# P15-EXP_IO.net
KiCad netlist of a schematic drawn in Altium Designer
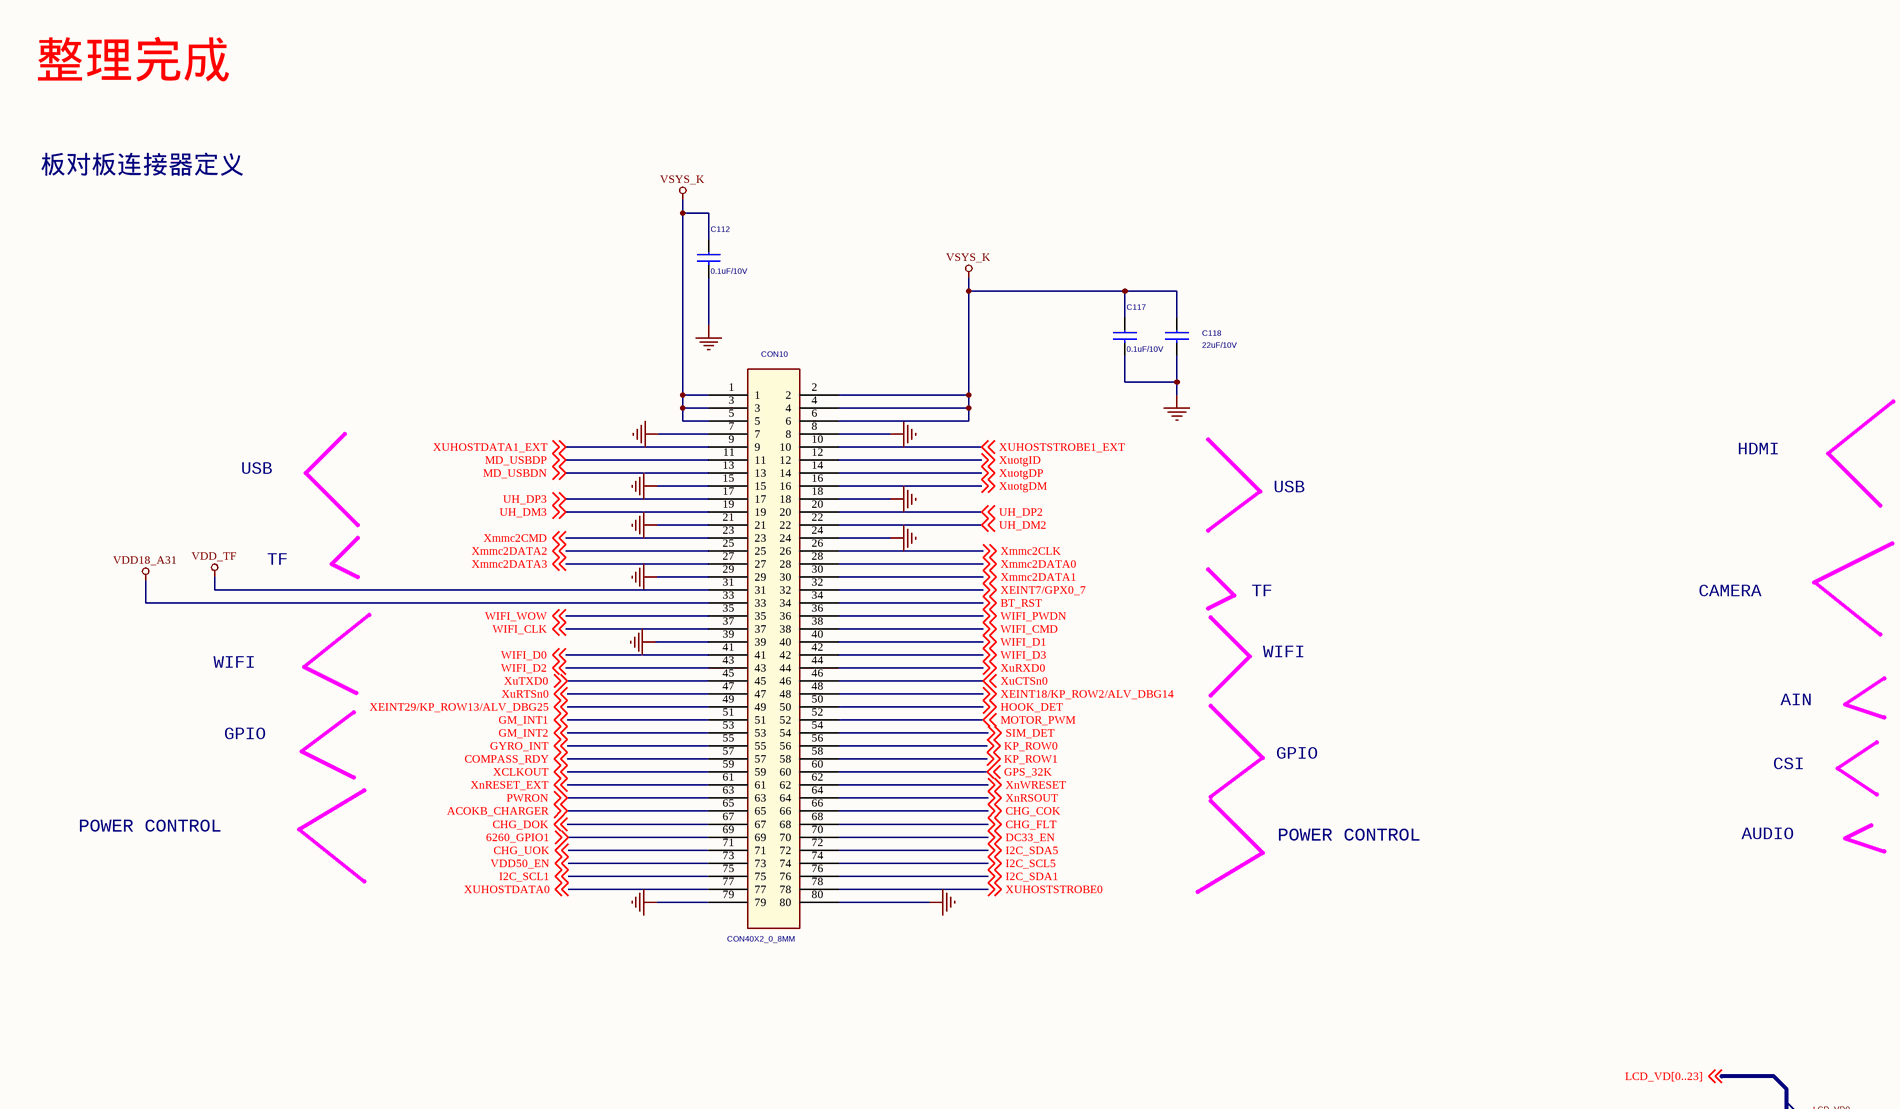
[diagram p0: P15-EXP_IO.SchDoc, top left]
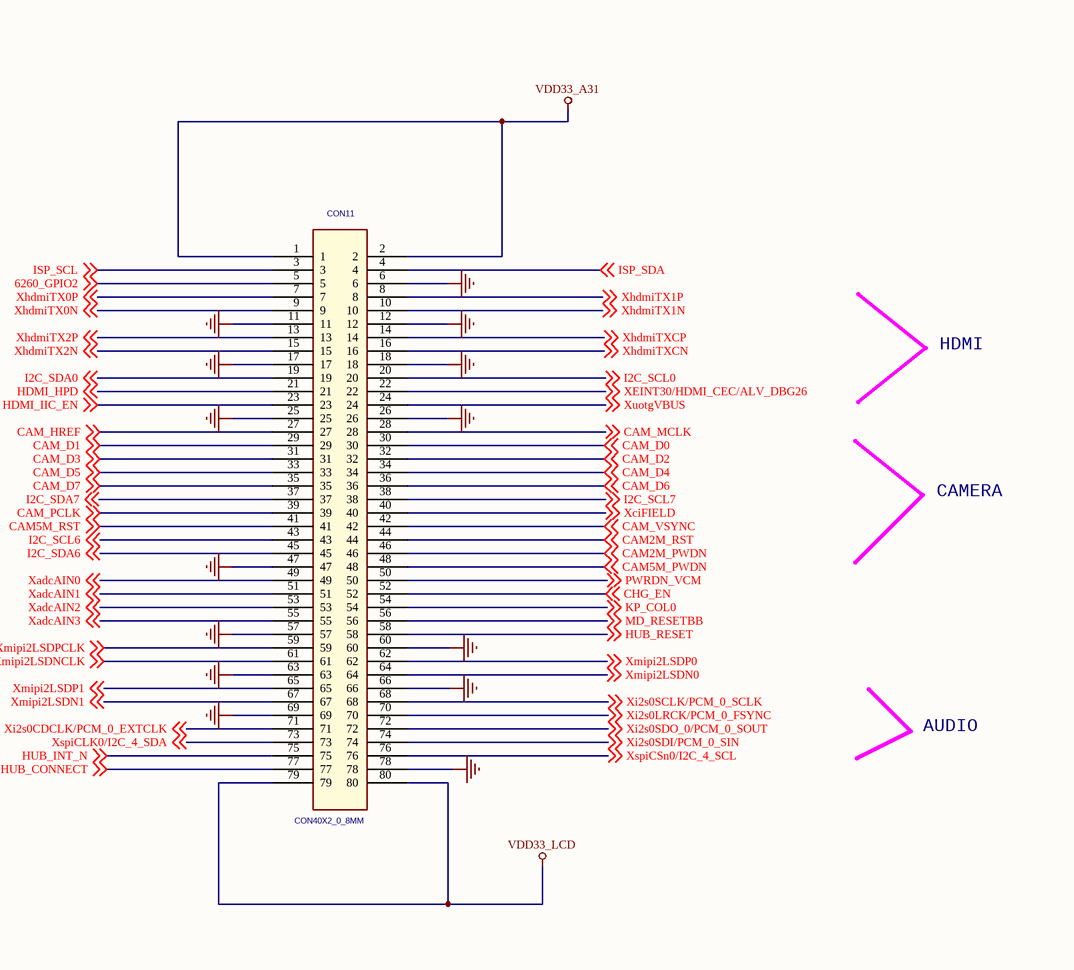
[diagram p1: P15-EXP_IO.SchDoc, top right]
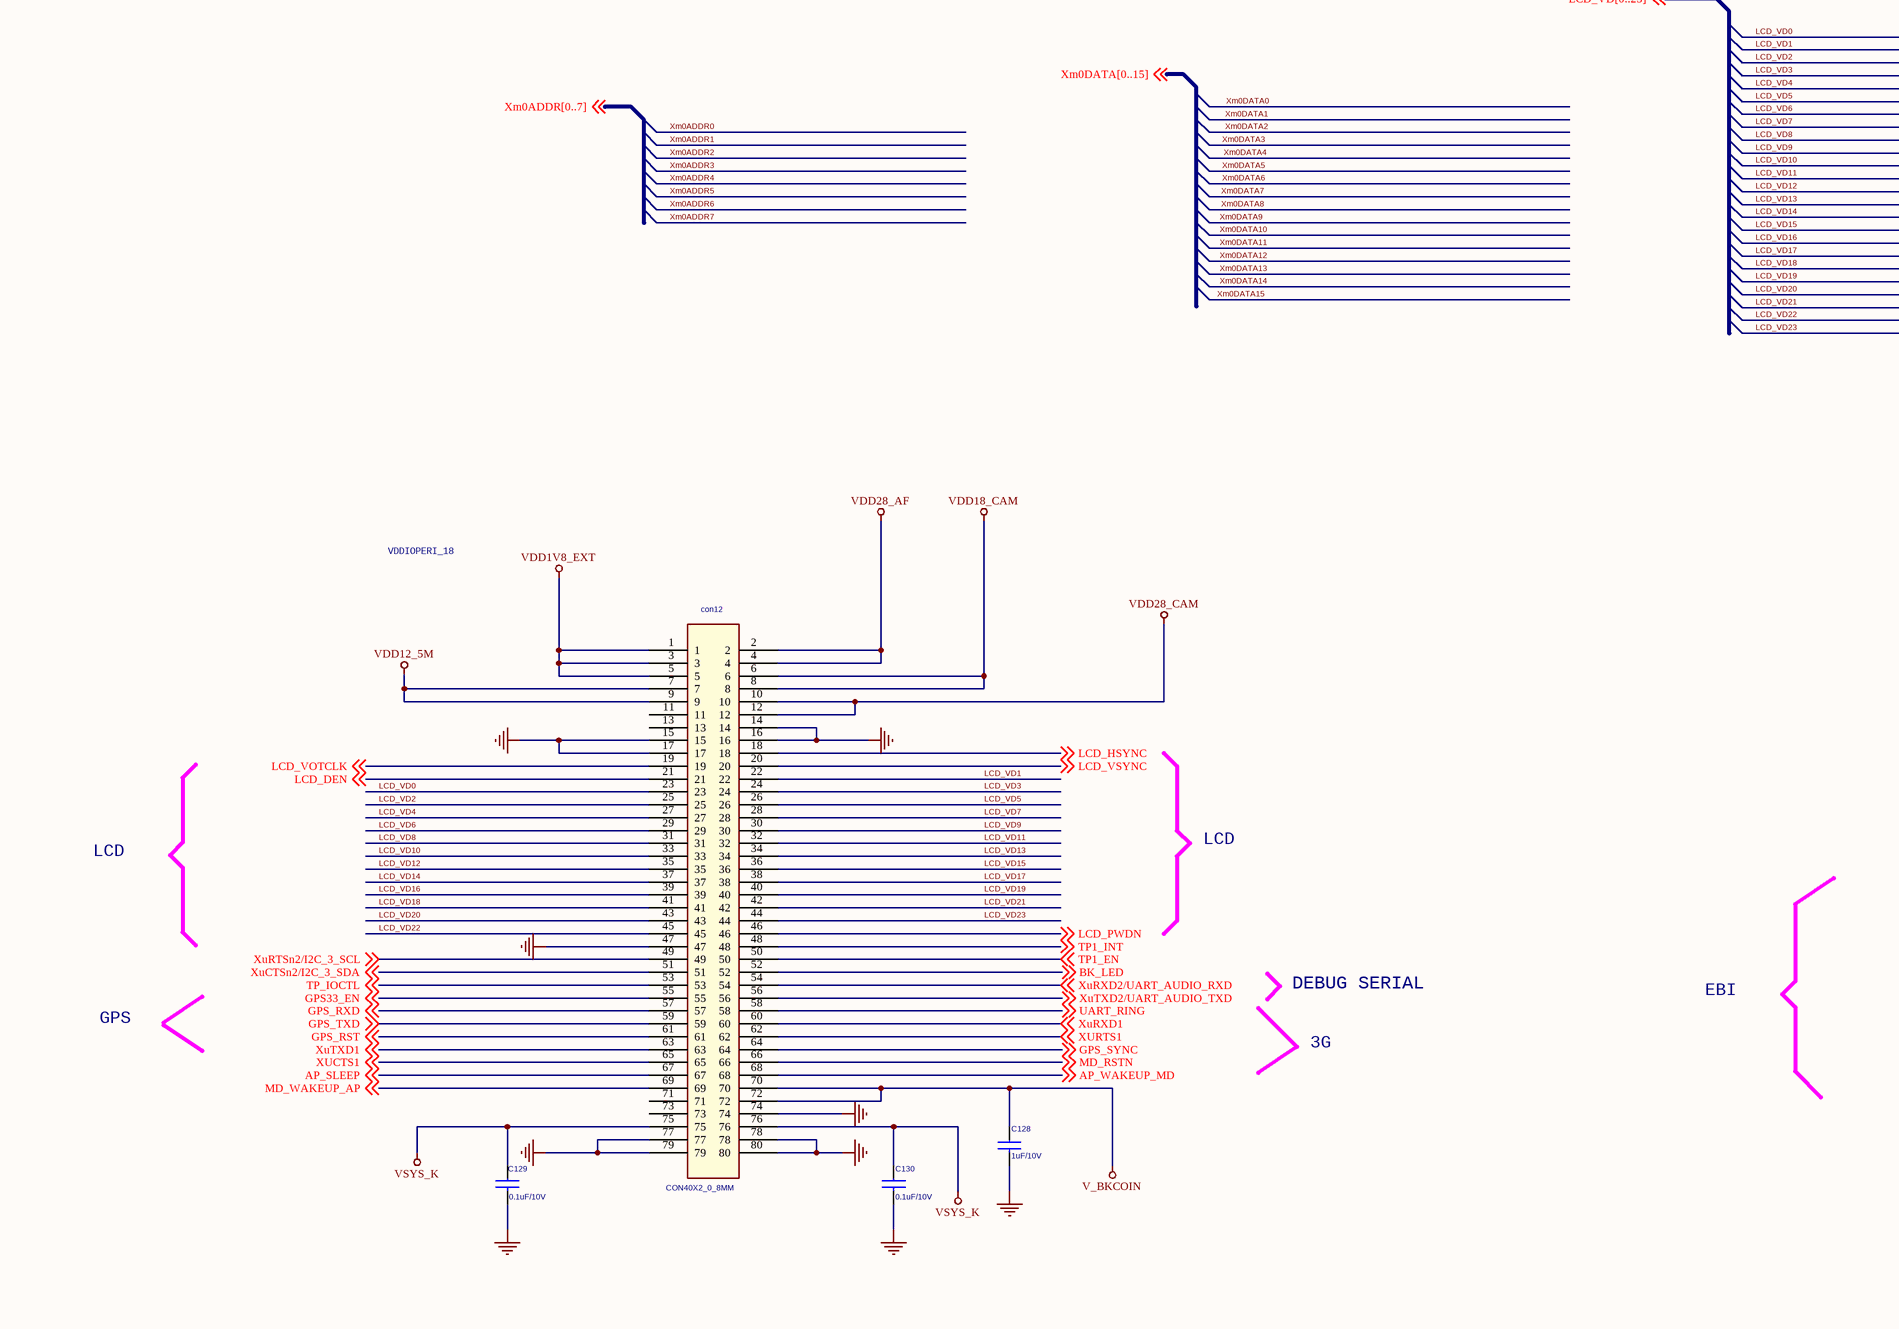
[diagram p2: P15-EXP_IO.SchDoc, bottom left]
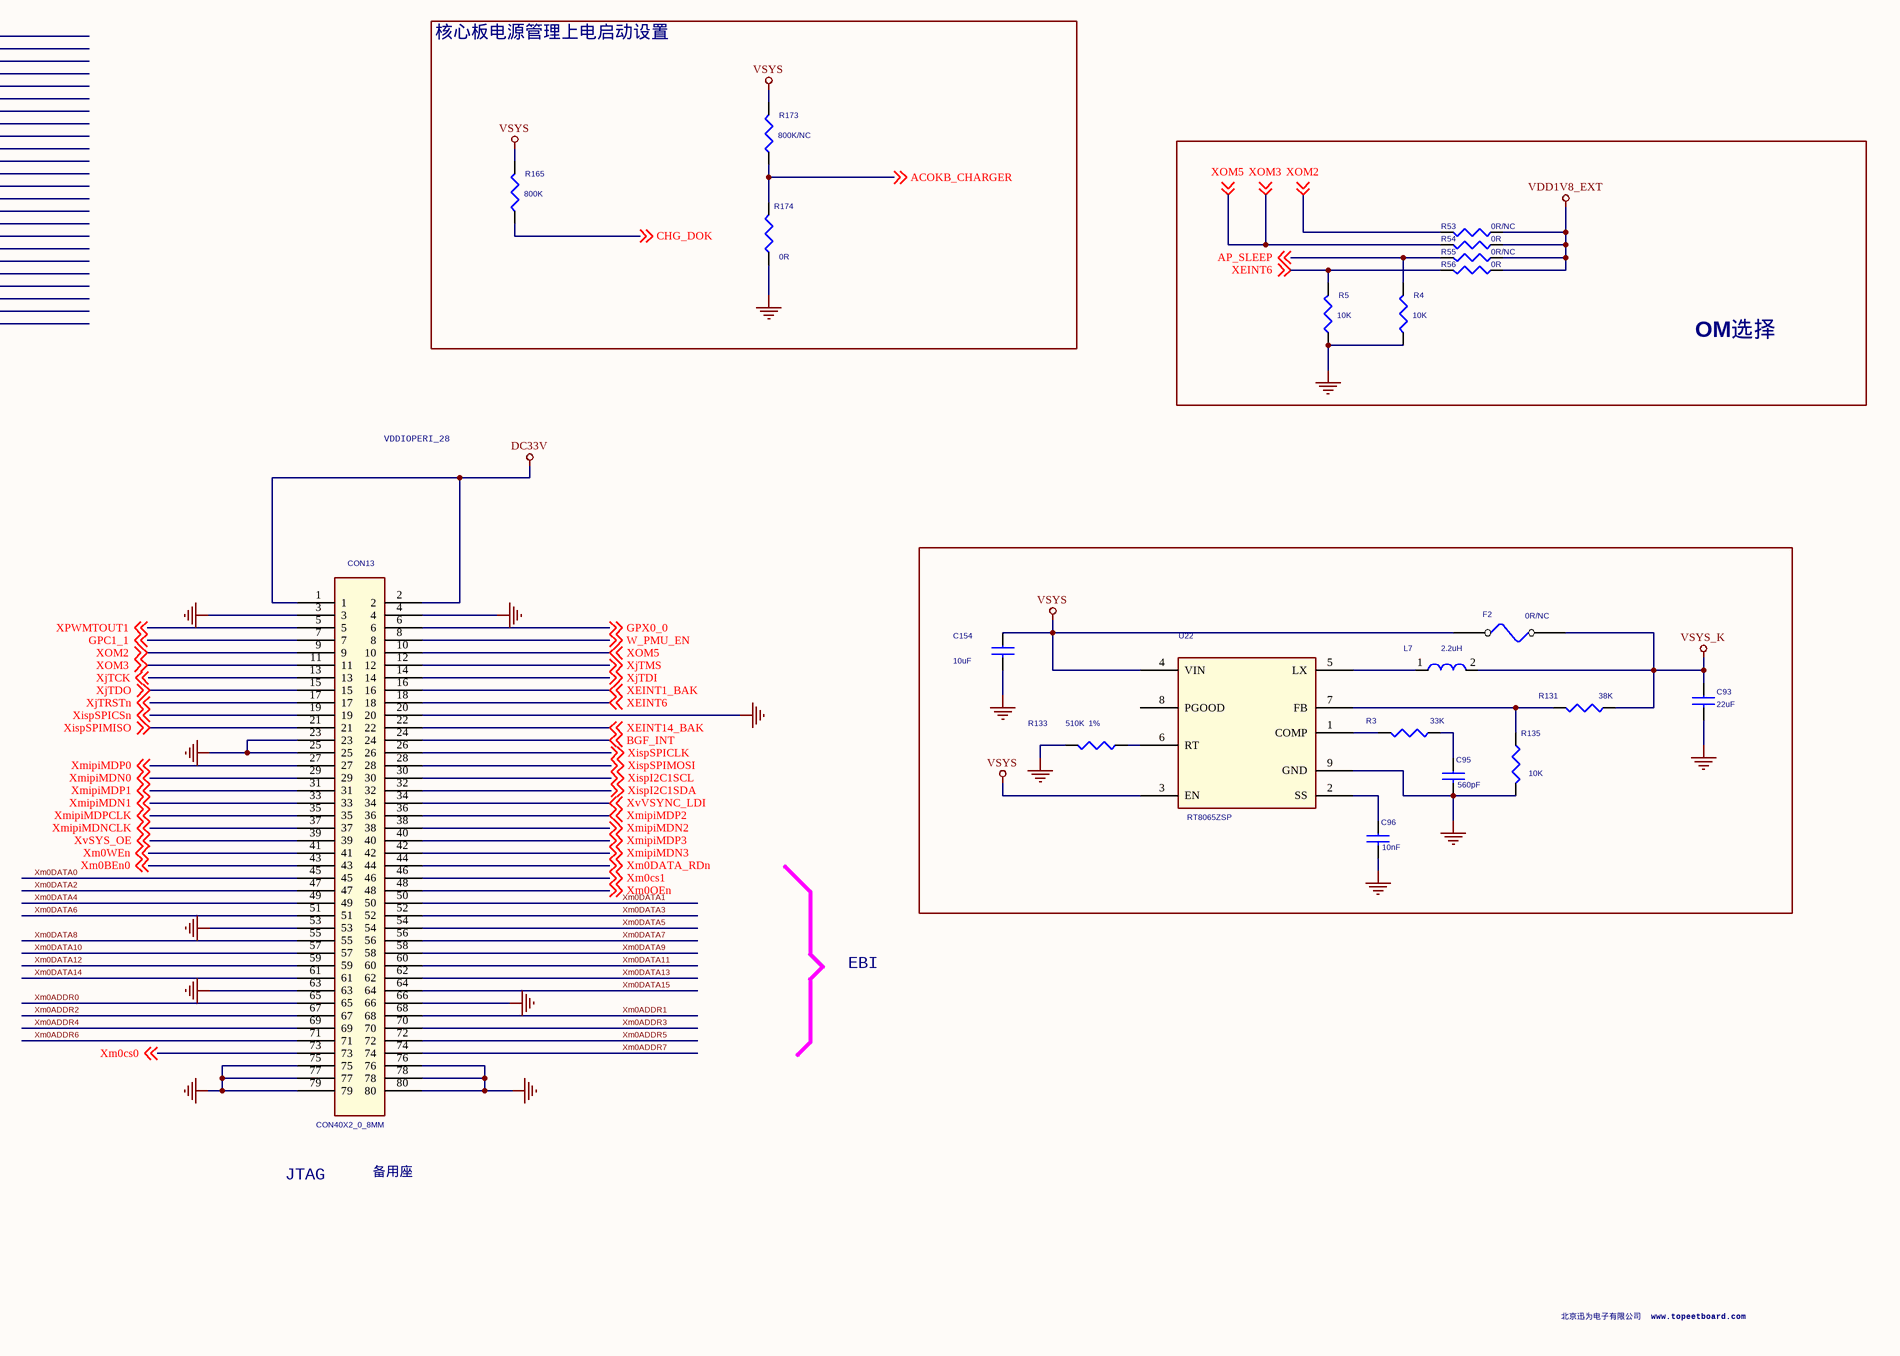
[diagram p3: P15-EXP_IO.SchDoc, bottom right]

(export (version "E")
  (design (tool "Eeschema 10.0.6"))
  (components
    (comp (ref "C93") (value "22uF") (footprint "C0805-S") (libsource (lib "*") (part "C1005")))
    (comp (ref "C95")
      (value "560pF")
      (footprint "C0603-S")
      (description "CER CHIP 1U 10% X5R 0402 10V  L/F")
      (fields (field (name "PART_NUMBER") "06-210594-01"))
      (libsource (lib "*") (part "CAP NP_3"))
    )
    (comp (ref "C96")
      (value "10nF")
      (footprint "C0603-S")
      (description "CER CHIP 1U 10% X5R 0402 10V  L/F")
      (fields (field (name "PART_NUMBER") "06-210594-01"))
      (libsource (lib "*") (part "CAP NP_3"))
    )
    (comp (ref "C112") (value "0.1uF/10V") (footprint "C0603-S") (libsource (lib "*") (part "C0402_0")))
    (comp (ref "C117") (value "0.1uF/10V") (footprint "C0603-S") (libsource (lib "*") (part "C0402_0")))
    (comp (ref "C118") (value "22uF/10V") (footprint "C1206-S") (libsource (lib "*") (part "C1206_0")))
    (comp (ref "C128") (value "1uF/10V") (footprint "C0603-S") (libsource (lib "*") (part "C0603_0")))
    (comp (ref "C129") (value "0.1uF/10V") (footprint "C0603-S") (libsource (lib "*") (part "C0402_0")))
    (comp (ref "C130") (value "0.1uF/10V") (footprint "C0603-S") (libsource (lib "*") (part "C0402_0")))
    (comp (ref "C154")
      (value "10uF")
      (footprint "C0603-S")
      (description "CER CHIP 1U 10% X5R 0402 10V  L/F")
      (fields (field (name "PART_NUMBER") "06-210594-01"))
      (libsource (lib "*") (part "CAP NP_3"))
    )
    (comp (ref "CON10") (value "CON40X2_0_8MM") (libsource (lib "*") (part "CON40X2_0_8MM")))
    (comp (ref "CON11") (value "CON40X2_0_8MM") (libsource (lib "*") (part "CON40X2_0_8MM")))
    (comp (ref "con12")
      (value "CON40X2_0_8MM")
      (footprint "CON2X40-0_5MM-BB")
      (libsource (lib "*") (part "CON40X2_0_8MM"))
    )
    (comp (ref "CON13") (value "CON40X2_0_8MM") (libsource (lib "*") (part "CON40X2_0_8MM")))
    (comp (ref "F2") (value "0R/NC") (libsource (lib "*") (part "FUSE")))
    (comp (ref "L7") (value "2.2uH") (footprint "L3X3MM") (libsource (lib "*") (part "LQH32C_0")))
    (comp (ref "R3") (value "33K") (footprint "R0603-S") (libsource (lib "*") (part "R1005_0")))
    (comp (ref "R4") (value "10K") (footprint "R0603-S") (libsource (lib "*") (part "R1005_0_Dup1")))
    (comp (ref "R5") (value "10K") (footprint "R0603-S") (libsource (lib "*") (part "R1005_0_Dup1")))
    (comp (ref "R53") (value "0R/NC") (footprint "R0603-S") (libsource (lib "*") (part "R1005_0_Dup1")))
    (comp (ref "R54") (value "0R") (footprint "R0603-S") (libsource (lib "*") (part "R1005_0_Dup1")))
    (comp (ref "R55") (value "0R/NC") (footprint "R0603-S") (libsource (lib "*") (part "R1005_0_Dup1")))
    (comp (ref "R56") (value "0R") (footprint "R0603-S") (libsource (lib "*") (part "R1005_0_Dup1")))
    (comp (ref "R131") (value "38K") (footprint "R0603-S") (libsource (lib "*") (part "R1005_0")))
    (comp (ref "R133") (value "510K  1%") (footprint "R0603-S") (libsource (lib "*") (part "R1005_0")))
    (comp (ref "R135") (value "10K") (footprint "R0603-S") (libsource (lib "*") (part "R1005_0")))
    (comp (ref "R165") (value "800K") (footprint "R0603-S") (libsource (lib "*") (part "R1005_0_Dup1")))
    (comp (ref "R173") (value "800K/NC") (footprint "R0603-S") (libsource (lib "*") (part "R1005_0_Dup1")))
    (comp (ref "R174") (value "0R") (footprint "R0603-S") (libsource (lib "*") (part "R1005_0_Dup1")))
    (comp (ref "U22") (value "RT8065ZSP") (libsource (lib "*") (part "RT8065_3")))
  )
  (nets
    (net (code "1") (name "6260_GPIO1") (class "Default")
      (node (ref "CON10") (pin "69") (pinfunction "69_69") (pintype "passive"))
    )
    (net (code "2") (name "6260_GPIO2") (class "Default")
      (node (ref "CON11") (pin "5") (pinfunction "5_5") (pintype "passive"))
    )
    (net (code "3") (name "ACOKB_CHARGER") (class "Default")
      (node (ref "CON10") (pin "65") (pinfunction "65_65") (pintype "passive"))
      (node (ref "R173") (pin "1") (pinfunction "1_1") (pintype "passive"))
      (node (ref "R174") (pin "2") (pinfunction "2_2") (pintype "passive"))
    )
    (net (code "4") (name "AP_SLEEP") (class "Default")
      (node (ref "R4") (pin "2") (pinfunction "2_2") (pintype "passive"))
      (node (ref "R55") (pin "2") (pinfunction "2_2") (pintype "passive"))
      (node (ref "con12") (pin "67") (pinfunction "67_67") (pintype "passive"))
    )
    (net (code "5") (name "AP_WAKEUP_MD") (class "Default")
      (node (ref "con12") (pin "68") (pinfunction "68_68") (pintype "passive"))
    )
    (net (code "6") (name "BGF_INT") (class "Default")
      (node (ref "CON13") (pin "24") (pinfunction "24_24") (pintype "passive"))
    )
    (net (code "7") (name "BK_LED") (class "Default")
      (node (ref "con12") (pin "52") (pinfunction "52_52") (pintype "passive"))
    )
    (net (code "8") (name "BT_RST") (class "Default")
      (node (ref "CON10") (pin "34") (pinfunction "34_34") (pintype "passive"))
    )
    (net (code "9") (name "CAM2M_PWDN") (class "Default")
      (node (ref "CON11") (pin "46") (pinfunction "46_46") (pintype "passive"))
    )
    (net (code "10") (name "CAM2M_RST") (class "Default")
      (node (ref "CON11") (pin "44") (pinfunction "44_44") (pintype "passive"))
    )
    (net (code "11") (name "CAM5M_PWDN") (class "Default")
      (node (ref "CON11") (pin "48") (pinfunction "48_48") (pintype "passive"))
    )
    (net (code "12") (name "CAM5M_RST") (class "Default")
      (node (ref "CON11") (pin "41") (pinfunction "41_41") (pintype "passive"))
    )
    (net (code "13") (name "CAM_D0") (class "Default")
      (node (ref "CON11") (pin "30") (pinfunction "30_30") (pintype "passive"))
    )
    (net (code "14") (name "CAM_D1") (class "Default")
      (node (ref "CON11") (pin "29") (pinfunction "29_29") (pintype "passive"))
    )
    (net (code "15") (name "CAM_D2") (class "Default")
      (node (ref "CON11") (pin "32") (pinfunction "32_32") (pintype "passive"))
    )
    (net (code "16") (name "CAM_D3") (class "Default")
      (node (ref "CON11") (pin "31") (pinfunction "31_31") (pintype "passive"))
    )
    (net (code "17") (name "CAM_D4") (class "Default")
      (node (ref "CON11") (pin "34") (pinfunction "34_34") (pintype "passive"))
    )
    (net (code "18") (name "CAM_D5") (class "Default")
      (node (ref "CON11") (pin "33") (pinfunction "33_33") (pintype "passive"))
    )
    (net (code "19") (name "CAM_D6") (class "Default")
      (node (ref "CON11") (pin "36") (pinfunction "36_36") (pintype "passive"))
    )
    (net (code "20") (name "CAM_D7") (class "Default")
      (node (ref "CON11") (pin "35") (pinfunction "35_35") (pintype "passive"))
    )
    (net (code "21") (name "CAM_HREF") (class "Default")
      (node (ref "CON11") (pin "27") (pinfunction "27_27") (pintype "passive"))
    )
    (net (code "22") (name "CAM_MCLK") (class "Default")
      (node (ref "CON11") (pin "28") (pinfunction "28_28") (pintype "passive"))
    )
    (net (code "23") (name "CAM_PCLK") (class "Default")
      (node (ref "CON11") (pin "39") (pinfunction "39_39") (pintype "passive"))
    )
    (net (code "24") (name "CAM_VSYNC") (class "Default")
      (node (ref "CON11") (pin "42") (pinfunction "42_42") (pintype "passive"))
    )
    (net (code "25") (name "CHG_COK") (class "Default")
      (node (ref "CON10") (pin "66") (pinfunction "66_66") (pintype "passive"))
    )
    (net (code "26") (name "CHG_DOK") (class "Default")
      (node (ref "CON10") (pin "67") (pinfunction "67_67") (pintype "passive"))
      (node (ref "R165") (pin "1") (pinfunction "1_1") (pintype "passive"))
    )
    (net (code "27") (name "CHG_EN") (class "Default")
      (node (ref "CON11") (pin "52") (pinfunction "52_52") (pintype "passive"))
    )
    (net (code "28") (name "CHG_FLT") (class "Default")
      (node (ref "CON10") (pin "68") (pinfunction "68_68") (pintype "passive"))
    )
    (net (code "29") (name "CHG_UOK") (class "Default")
      (node (ref "CON10") (pin "71") (pinfunction "71_71") (pintype "passive"))
    )
    (net (code "30") (name "COMPASS_RDY") (class "Default")
      (node (ref "CON10") (pin "57") (pinfunction "57_57") (pintype "passive"))
    )
    (net (code "31") (name "DC33V") (class "Default")
      (node (ref "CON13") (pin "1") (pinfunction "1_1") (pintype "passive"))
      (node (ref "CON13") (pin "2") (pinfunction "2_2") (pintype "passive"))
    )
    (net (code "32") (name "DC33_EN") (class "Default")
      (node (ref "CON10") (pin "70") (pinfunction "70_70") (pintype "passive"))
    )
    (net (code "33") (name "GM_INT1") (class "Default")
      (node (ref "CON10") (pin "51") (pinfunction "51_51") (pintype "passive"))
    )
    (net (code "34") (name "GM_INT2") (class "Default")
      (node (ref "CON10") (pin "53") (pinfunction "53_53") (pintype "passive"))
    )
    (net (code "35") (name "GND") (class "Default")
      (node (ref "C112") (pin "2") (pinfunction "2_2") (pintype "passive"))
      (node (ref "C117") (pin "2") (pinfunction "2_2") (pintype "passive"))
      (node (ref "C118") (pin "2") (pinfunction "2_2") (pintype "passive"))
      (node (ref "C128") (pin "2") (pinfunction "2_2") (pintype "passive"))
      (node (ref "C129") (pin "2") (pinfunction "2_2") (pintype "passive"))
      (node (ref "C130") (pin "2") (pinfunction "2_2") (pintype "passive"))
      (node (ref "C154") (pin "2") (pinfunction "2_2") (pintype "passive"))
      (node (ref "C93") (pin "2") (pinfunction "2_2") (pintype "passive"))
      (node (ref "C95") (pin "2") (pinfunction "2_2") (pintype "passive"))
      (node (ref "C96") (pin "2") (pinfunction "2_2") (pintype "passive"))
      (node (ref "CON10") (pin "15") (pinfunction "15_15") (pintype "passive"))
      (node (ref "CON10") (pin "18") (pinfunction "18_18") (pintype "passive"))
      (node (ref "CON10") (pin "21") (pinfunction "21_21") (pintype "passive"))
      (node (ref "CON10") (pin "24") (pinfunction "24_24") (pintype "passive"))
      (node (ref "CON10") (pin "29") (pinfunction "29_29") (pintype "passive"))
      (node (ref "CON10") (pin "39") (pinfunction "39_39") (pintype "passive"))
      (node (ref "CON10") (pin "7") (pinfunction "7_7") (pintype "passive"))
      (node (ref "CON10") (pin "79") (pinfunction "79_79") (pintype "passive"))
      (node (ref "CON10") (pin "8") (pinfunction "8_8") (pintype "passive"))
      (node (ref "CON10") (pin "80") (pinfunction "80_80") (pintype "passive"))
      (node (ref "CON11") (pin "11") (pinfunction "11_11") (pintype "passive"))
      (node (ref "CON11") (pin "12") (pinfunction "12_12") (pintype "passive"))
      (node (ref "CON11") (pin "17") (pinfunction "17_17") (pintype "passive"))
      (node (ref "CON11") (pin "18") (pinfunction "18_18") (pintype "passive"))
      (node (ref "CON11") (pin "25") (pinfunction "25_25") (pintype "passive"))
      (node (ref "CON11") (pin "26") (pinfunction "26_26") (pintype "passive"))
      (node (ref "CON11") (pin "47") (pinfunction "47_47") (pintype "passive"))
      (node (ref "CON11") (pin "57") (pinfunction "57_57") (pintype "passive"))
      (node (ref "CON11") (pin "6") (pinfunction "6_6") (pintype "passive"))
      (node (ref "CON11") (pin "60") (pinfunction "60_60") (pintype "passive"))
      (node (ref "CON11") (pin "63") (pinfunction "63_63") (pintype "passive"))
      (node (ref "CON11") (pin "66") (pinfunction "66_66") (pintype "passive"))
      (node (ref "CON11") (pin "69") (pinfunction "69_69") (pintype "passive"))
      (node (ref "CON11") (pin "78") (pinfunction "78_78") (pintype "passive"))
      (node (ref "CON13") (pin "20") (pinfunction "20_20") (pintype "passive"))
      (node (ref "CON13") (pin "23") (pinfunction "23_23") (pintype "passive"))
      (node (ref "CON13") (pin "25") (pinfunction "25_25") (pintype "passive"))
      (node (ref "CON13") (pin "3") (pinfunction "3_3") (pintype "passive"))
      (node (ref "CON13") (pin "4") (pinfunction "4_4") (pintype "passive"))
      (node (ref "CON13") (pin "53") (pinfunction "53_53") (pintype "passive"))
      (node (ref "CON13") (pin "63") (pinfunction "63_63") (pintype "passive"))
      (node (ref "CON13") (pin "66") (pinfunction "66_66") (pintype "passive"))
      (node (ref "CON13") (pin "75") (pinfunction "75_75") (pintype "passive"))
      (node (ref "CON13") (pin "76") (pinfunction "76_76") (pintype "passive"))
      (node (ref "CON13") (pin "77") (pinfunction "77_77") (pintype "passive"))
      (node (ref "CON13") (pin "78") (pinfunction "78_78") (pintype "passive"))
      (node (ref "CON13") (pin "79") (pinfunction "79_79") (pintype "passive"))
      (node (ref "CON13") (pin "80") (pinfunction "80_80") (pintype "passive"))
      (node (ref "R133") (pin "2") (pinfunction "2_2") (pintype "passive"))
      (node (ref "R135") (pin "2") (pinfunction "2_2") (pintype "passive"))
      (node (ref "R174") (pin "1") (pinfunction "1_1") (pintype "passive"))
      (node (ref "R4") (pin "1") (pinfunction "1_1") (pintype "passive"))
      (node (ref "R5") (pin "1") (pinfunction "1_1") (pintype "passive"))
      (node (ref "U22") (pin "9") (pinfunction "GND_9") (pintype "passive"))
      (node (ref "con12") (pin "14") (pinfunction "14_14") (pintype "passive"))
      (node (ref "con12") (pin "15") (pinfunction "15_15") (pintype "passive"))
      (node (ref "con12") (pin "16") (pinfunction "16_16") (pintype "passive"))
      (node (ref "con12") (pin "17") (pinfunction "17_17") (pintype "passive"))
      (node (ref "con12") (pin "47") (pinfunction "47_47") (pintype "passive"))
      (node (ref "con12") (pin "74") (pinfunction "74_74") (pintype "passive"))
      (node (ref "con12") (pin "77") (pinfunction "77_77") (pintype "passive"))
      (node (ref "con12") (pin "78") (pinfunction "78_78") (pintype "passive"))
      (node (ref "con12") (pin "79") (pinfunction "79_79") (pintype "passive"))
      (node (ref "con12") (pin "80") (pinfunction "80_80") (pintype "passive"))
    )
    (net (code "36") (name "GPC1_1") (class "Default")
      (node (ref "CON13") (pin "7") (pinfunction "7_7") (pintype "passive"))
    )
    (net (code "37") (name "GPS33_EN") (class "Default")
      (node (ref "con12") (pin "55") (pinfunction "55_55") (pintype "passive"))
    )
    (net (code "38") (name "GPS_32K") (class "Default")
      (node (ref "CON10") (pin "60") (pinfunction "60_60") (pintype "passive"))
    )
    (net (code "39") (name "GPS_RST") (class "Default")
      (node (ref "con12") (pin "61") (pinfunction "61_61") (pintype "passive"))
    )
    (net (code "40") (name "GPS_RXD") (class "Default")
      (node (ref "con12") (pin "57") (pinfunction "57_57") (pintype "passive"))
    )
    (net (code "41") (name "GPS_SYNC") (class "Default")
      (node (ref "con12") (pin "64") (pinfunction "64_64") (pintype "passive"))
    )
    (net (code "42") (name "GPS_TXD") (class "Default")
      (node (ref "con12") (pin "59") (pinfunction "59_59") (pintype "passive"))
    )
    (net (code "43") (name "GPX0_0") (class "Default")
      (node (ref "CON13") (pin "6") (pinfunction "6_6") (pintype "passive"))
    )
    (net (code "44") (name "GYRO_INT") (class "Default")
      (node (ref "CON10") (pin "55") (pinfunction "55_55") (pintype "passive"))
    )
    (net (code "45") (name "HDMI_HPD") (class "Default")
      (node (ref "CON11") (pin "21") (pinfunction "21_21") (pintype "passive"))
    )
    (net (code "46") (name "HDMI_IIC_EN") (class "Default")
      (node (ref "CON11") (pin "23") (pinfunction "23_23") (pintype "passive"))
    )
    (net (code "47") (name "HOOK_DET") (class "Default")
      (node (ref "CON10") (pin "50") (pinfunction "50_50") (pintype "passive"))
    )
    (net (code "48") (name "HUB_CONNECT") (class "Default")
      (node (ref "CON11") (pin "77") (pinfunction "77_77") (pintype "passive"))
    )
    (net (code "49") (name "HUB_INT_N") (class "Default")
      (node (ref "CON11") (pin "75") (pinfunction "75_75") (pintype "passive"))
    )
    (net (code "50") (name "HUB_RESET") (class "Default")
      (node (ref "CON11") (pin "58") (pinfunction "58_58") (pintype "passive"))
    )
    (net (code "51") (name "I2C_SCL0") (class "Default")
      (node (ref "CON11") (pin "20") (pinfunction "20_20") (pintype "passive"))
    )
    (net (code "52") (name "I2C_SCL1") (class "Default")
      (node (ref "CON10") (pin "75") (pinfunction "75_75") (pintype "passive"))
    )
    (net (code "53") (name "I2C_SCL5") (class "Default")
      (node (ref "CON10") (pin "74") (pinfunction "74_74") (pintype "passive"))
    )
    (net (code "54") (name "I2C_SCL6") (class "Default")
      (node (ref "CON11") (pin "43") (pinfunction "43_43") (pintype "passive"))
    )
    (net (code "55") (name "I2C_SCL7") (class "Default")
      (node (ref "CON11") (pin "38") (pinfunction "38_38") (pintype "passive"))
    )
    (net (code "56") (name "I2C_SDA0") (class "Default")
      (node (ref "CON11") (pin "19") (pinfunction "19_19") (pintype "passive"))
    )
    (net (code "57") (name "I2C_SDA1") (class "Default")
      (node (ref "CON10") (pin "76") (pinfunction "76_76") (pintype "passive"))
    )
    (net (code "58") (name "I2C_SDA5") (class "Default")
      (node (ref "CON10") (pin "72") (pinfunction "72_72") (pintype "passive"))
    )
    (net (code "59") (name "I2C_SDA6") (class "Default")
      (node (ref "CON11") (pin "45") (pinfunction "45_45") (pintype "passive"))
    )
    (net (code "60") (name "I2C_SDA7") (class "Default")
      (node (ref "CON11") (pin "37") (pinfunction "37_37") (pintype "passive"))
    )
    (net (code "61") (name "ISP_SCL") (class "Default")
      (node (ref "CON11") (pin "3") (pinfunction "3_3") (pintype "passive"))
    )
    (net (code "62") (name "ISP_SDA") (class "Default")
      (node (ref "CON11") (pin "4") (pinfunction "4_4") (pintype "passive"))
    )
    (net (code "63") (name "KP_COL0") (class "Default")
      (node (ref "CON11") (pin "54") (pinfunction "54_54") (pintype "passive"))
    )
    (net (code "64") (name "KP_ROW0") (class "Default")
      (node (ref "CON10") (pin "56") (pinfunction "56_56") (pintype "passive"))
    )
    (net (code "65") (name "KP_ROW1") (class "Default")
      (node (ref "CON10") (pin "58") (pinfunction "58_58") (pintype "passive"))
    )
    (net (code "66") (name "LCD_DEN") (class "Default")
      (node (ref "con12") (pin "21") (pinfunction "21_21") (pintype "passive"))
    )
    (net (code "67") (name "LCD_HSYNC") (class "Default")
      (node (ref "con12") (pin "18") (pinfunction "18_18") (pintype "passive"))
    )
    (net (code "68") (name "LCD_PWDN") (class "Default")
      (node (ref "con12") (pin "46") (pinfunction "46_46") (pintype "passive"))
    )
    (net (code "69") (name "LCD_VD0") (class "Default")
      (node (ref "con12") (pin "23") (pinfunction "23_23") (pintype "passive"))
    )
    (net (code "70") (name "LCD_VD1") (class "Default")
      (node (ref "con12") (pin "22") (pinfunction "22_22") (pintype "passive"))
    )
    (net (code "71") (name "LCD_VD2") (class "Default")
      (node (ref "con12") (pin "25") (pinfunction "25_25") (pintype "passive"))
    )
    (net (code "72") (name "LCD_VD3") (class "Default")
      (node (ref "con12") (pin "24") (pinfunction "24_24") (pintype "passive"))
    )
    (net (code "73") (name "LCD_VD4") (class "Default")
      (node (ref "con12") (pin "27") (pinfunction "27_27") (pintype "passive"))
    )
    (net (code "74") (name "LCD_VD5") (class "Default")
      (node (ref "con12") (pin "26") (pinfunction "26_26") (pintype "passive"))
    )
    (net (code "75") (name "LCD_VD6") (class "Default")
      (node (ref "con12") (pin "29") (pinfunction "29_29") (pintype "passive"))
    )
    (net (code "76") (name "LCD_VD7") (class "Default")
      (node (ref "con12") (pin "28") (pinfunction "28_28") (pintype "passive"))
    )
    (net (code "77") (name "LCD_VD8") (class "Default")
      (node (ref "con12") (pin "31") (pinfunction "31_31") (pintype "passive"))
    )
    (net (code "78") (name "LCD_VD9") (class "Default")
      (node (ref "con12") (pin "30") (pinfunction "30_30") (pintype "passive"))
    )
    (net (code "79") (name "LCD_VD10") (class "Default")
      (node (ref "con12") (pin "33") (pinfunction "33_33") (pintype "passive"))
    )
    (net (code "80") (name "LCD_VD11") (class "Default")
      (node (ref "con12") (pin "32") (pinfunction "32_32") (pintype "passive"))
    )
    (net (code "81") (name "LCD_VD12") (class "Default")
      (node (ref "con12") (pin "35") (pinfunction "35_35") (pintype "passive"))
    )
    (net (code "82") (name "LCD_VD13") (class "Default")
      (node (ref "con12") (pin "34") (pinfunction "34_34") (pintype "passive"))
    )
    (net (code "83") (name "LCD_VD14") (class "Default")
      (node (ref "con12") (pin "37") (pinfunction "37_37") (pintype "passive"))
    )
    (net (code "84") (name "LCD_VD15") (class "Default")
      (node (ref "con12") (pin "36") (pinfunction "36_36") (pintype "passive"))
    )
    (net (code "85") (name "LCD_VD16") (class "Default")
      (node (ref "con12") (pin "39") (pinfunction "39_39") (pintype "passive"))
    )
    (net (code "86") (name "LCD_VD17") (class "Default")
      (node (ref "con12") (pin "38") (pinfunction "38_38") (pintype "passive"))
    )
    (net (code "87") (name "LCD_VD18") (class "Default")
      (node (ref "con12") (pin "41") (pinfunction "41_41") (pintype "passive"))
    )
    (net (code "88") (name "LCD_VD19") (class "Default")
      (node (ref "con12") (pin "40") (pinfunction "40_40") (pintype "passive"))
    )
    (net (code "89") (name "LCD_VD20") (class "Default")
      (node (ref "con12") (pin "43") (pinfunction "43_43") (pintype "passive"))
    )
    (net (code "90") (name "LCD_VD21") (class "Default")
      (node (ref "con12") (pin "42") (pinfunction "42_42") (pintype "passive"))
    )
    (net (code "91") (name "LCD_VD22") (class "Default")
      (node (ref "con12") (pin "45") (pinfunction "45_45") (pintype "passive"))
    )
    (net (code "92") (name "LCD_VD23") (class "Default")
      (node (ref "con12") (pin "44") (pinfunction "44_44") (pintype "passive"))
    )
    (net (code "94") (name "LCD_VOTCLK") (class "Default")
      (node (ref "con12") (pin "19") (pinfunction "19_19") (pintype "passive"))
    )
    (net (code "95") (name "LCD_VSYNC") (class "Default")
      (node (ref "con12") (pin "20") (pinfunction "20_20") (pintype "passive"))
    )
    (net (code "96") (name "MD_RESETBB") (class "Default")
      (node (ref "CON11") (pin "56") (pinfunction "56_56") (pintype "passive"))
    )
    (net (code "97") (name "MD_RSTN") (class "Default")
      (node (ref "con12") (pin "66") (pinfunction "66_66") (pintype "passive"))
    )
    (net (code "98") (name "MD_USBDN") (class "Default")
      (node (ref "CON10") (pin "13") (pinfunction "13_13") (pintype "passive"))
    )
    (net (code "99") (name "MD_USBDP") (class "Default")
      (node (ref "CON10") (pin "11") (pinfunction "11_11") (pintype "passive"))
    )
    (net (code "100") (name "MD_WAKEUP_AP") (class "Default")
      (node (ref "con12") (pin "69") (pinfunction "69_69") (pintype "passive"))
    )
    (net (code "101") (name "MOTOR_PWM") (class "Default")
      (node (ref "CON10") (pin "52") (pinfunction "52_52") (pintype "passive"))
    )
    (net (code "102") (name "Net-(C95-Pad1)") (class "Default")
      (node (ref "C95") (pin "1") (pinfunction "1_1") (pintype "passive"))
      (node (ref "R3") (pin "1") (pinfunction "1_1") (pintype "passive"))
    )
    (net (code "103") (name "Net-(U22-COMP)") (class "Default")
      (node (ref "R3") (pin "2") (pinfunction "2_2") (pintype "passive"))
      (node (ref "U22") (pin "1") (pinfunction "COMP_1") (pintype "passive"))
    )
    (net (code "104") (name "Net-(U22-FB)") (class "Default")
      (node (ref "R131") (pin "2") (pinfunction "2_2") (pintype "passive"))
      (node (ref "R135") (pin "1") (pinfunction "1_1") (pintype "passive"))
      (node (ref "U22") (pin "7") (pinfunction "FB_7") (pintype "passive"))
    )
    (net (code "105") (name "Net-(U22-LX)") (class "Default")
      (node (ref "L7") (pin "1") (pinfunction "1_1") (pintype "passive"))
      (node (ref "U22") (pin "5") (pinfunction "LX_5") (pintype "passive"))
    )
    (net (code "106") (name "Net-(U22-RT)") (class "Default")
      (node (ref "R133") (pin "1") (pinfunction "1_1") (pintype "passive"))
      (node (ref "U22") (pin "6") (pinfunction "RT_6") (pintype "passive"))
    )
    (net (code "107") (name "Net-(U22-SS)") (class "Default")
      (node (ref "C96") (pin "1") (pinfunction "1_1") (pintype "passive"))
      (node (ref "U22") (pin "2") (pinfunction "SS_2") (pintype "passive"))
    )
    (net (code "108") (name "PWRDN_VCM") (class "Default")
      (node (ref "CON11") (pin "50") (pinfunction "50_50") (pintype "passive"))
    )
    (net (code "109") (name "PWRON") (class "Default")
      (node (ref "CON10") (pin "63") (pinfunction "63_63") (pintype "passive"))
    )
    (net (code "110") (name "SIM_DET") (class "Default")
      (node (ref "CON10") (pin "54") (pinfunction "54_54") (pintype "passive"))
    )
    (net (code "111") (name "TP1_EN") (class "Default")
      (node (ref "con12") (pin "50") (pinfunction "50_50") (pintype "passive"))
    )
    (net (code "112") (name "TP1_INT") (class "Default")
      (node (ref "con12") (pin "48") (pinfunction "48_48") (pintype "passive"))
    )
    (net (code "113") (name "TP_IOCTL") (class "Default")
      (node (ref "con12") (pin "53") (pinfunction "53_53") (pintype "passive"))
    )
    (net (code "114") (name "UART_RING") (class "Default")
      (node (ref "con12") (pin "58") (pinfunction "58_58") (pintype "passive"))
    )
    (net (code "115") (name "UH_DM2") (class "Default")
      (node (ref "CON10") (pin "22") (pinfunction "22_22") (pintype "passive"))
    )
    (net (code "116") (name "UH_DM3") (class "Default")
      (node (ref "CON10") (pin "19") (pinfunction "19_19") (pintype "passive"))
    )
    (net (code "117") (name "UH_DP2") (class "Default")
      (node (ref "CON10") (pin "20") (pinfunction "20_20") (pintype "passive"))
    )
    (net (code "118") (name "UH_DP3") (class "Default")
      (node (ref "CON10") (pin "17") (pinfunction "17_17") (pintype "passive"))
    )
    (net (code "119") (name "VDD1V8_EXT") (class "Default")
      (node (ref "R53") (pin "1") (pinfunction "1_1") (pintype "passive"))
      (node (ref "R54") (pin "1") (pinfunction "1_1") (pintype "passive"))
      (node (ref "R55") (pin "1") (pinfunction "1_1") (pintype "passive"))
      (node (ref "R56") (pin "1") (pinfunction "1_1") (pintype "passive"))
      (node (ref "con12") (pin "1") (pinfunction "1_1") (pintype "passive"))
      (node (ref "con12") (pin "3") (pinfunction "3_3") (pintype "passive"))
      (node (ref "con12") (pin "5") (pinfunction "5_5") (pintype "passive"))
    )
    (net (code "120") (name "VDD12_5M") (class "Default")
      (node (ref "con12") (pin "7") (pinfunction "7_7") (pintype "passive"))
      (node (ref "con12") (pin "9") (pinfunction "9_9") (pintype "passive"))
    )
    (net (code "121") (name "VDD18_A31") (class "Default")
      (node (ref "CON10") (pin "33") (pinfunction "33_33") (pintype "passive"))
    )
    (net (code "122") (name "VDD18_CAM") (class "Default")
      (node (ref "con12") (pin "6") (pinfunction "6_6") (pintype "passive"))
      (node (ref "con12") (pin "8") (pinfunction "8_8") (pintype "passive"))
    )
    (net (code "123") (name "VDD28_AF") (class "Default")
      (node (ref "con12") (pin "2") (pinfunction "2_2") (pintype "passive"))
      (node (ref "con12") (pin "4") (pinfunction "4_4") (pintype "passive"))
    )
    (net (code "124") (name "VDD28_CAM") (class "Default")
      (node (ref "con12") (pin "10") (pinfunction "10_10") (pintype "passive"))
      (node (ref "con12") (pin "12") (pinfunction "12_12") (pintype "passive"))
    )
    (net (code "125") (name "VDD33_A31") (class "Default")
      (node (ref "CON11") (pin "1") (pinfunction "1_1") (pintype "passive"))
      (node (ref "CON11") (pin "2") (pinfunction "2_2") (pintype "passive"))
    )
    (net (code "126") (name "VDD33_LCD") (class "Default")
      (node (ref "CON11") (pin "79") (pinfunction "79_79") (pintype "passive"))
      (node (ref "CON11") (pin "80") (pinfunction "80_80") (pintype "passive"))
    )
    (net (code "127") (name "VDD50_EN") (class "Default")
      (node (ref "CON10") (pin "73") (pinfunction "73_73") (pintype "passive"))
    )
    (net (code "128") (name "VDD_TF") (class "Default")
      (node (ref "CON10") (pin "31") (pinfunction "31_31") (pintype "passive"))
    )
    (net (code "129") (name "VSYS") (class "Default")
      (node (ref "C154") (pin "1") (pinfunction "1_1") (pintype "passive"))
      (node (ref "F2") (pin "1") (pinfunction "1_1") (pintype "passive"))
      (node (ref "R165") (pin "2") (pinfunction "2_2") (pintype "passive"))
      (node (ref "R173") (pin "2") (pinfunction "2_2") (pintype "passive"))
      (node (ref "U22") (pin "3") (pinfunction "EN_3") (pintype "passive"))
      (node (ref "U22") (pin "4") (pinfunction "VIN_4") (pintype "passive"))
    )
    (net (code "130") (name "VSYS_K") (class "Default")
      (node (ref "C112") (pin "1") (pinfunction "1_1") (pintype "passive"))
      (node (ref "C117") (pin "1") (pinfunction "1_1") (pintype "passive"))
      (node (ref "C118") (pin "1") (pinfunction "1_1") (pintype "passive"))
      (node (ref "C129") (pin "1") (pinfunction "1_1") (pintype "passive"))
      (node (ref "C130") (pin "1") (pinfunction "1_1") (pintype "passive"))
      (node (ref "C93") (pin "1") (pinfunction "1_1") (pintype "passive"))
      (node (ref "CON10") (pin "1") (pinfunction "1_1") (pintype "passive"))
      (node (ref "CON10") (pin "2") (pinfunction "2_2") (pintype "passive"))
      (node (ref "CON10") (pin "3") (pinfunction "3_3") (pintype "passive"))
      (node (ref "CON10") (pin "4") (pinfunction "4_4") (pintype "passive"))
      (node (ref "CON10") (pin "5") (pinfunction "5_5") (pintype "passive"))
      (node (ref "CON10") (pin "6") (pinfunction "6_6") (pintype "passive"))
      (node (ref "F2") (pin "2") (pinfunction "2_2") (pintype "passive"))
      (node (ref "L7") (pin "2") (pinfunction "2_2") (pintype "passive"))
      (node (ref "R131") (pin "1") (pinfunction "1_1") (pintype "passive"))
      (node (ref "con12") (pin "75") (pinfunction "75_75") (pintype "passive"))
      (node (ref "con12") (pin "76") (pinfunction "76_76") (pintype "passive"))
    )
    (net (code "131") (name "V_BKCOIN") (class "Default")
      (node (ref "C128") (pin "1") (pinfunction "1_1") (pintype "passive"))
      (node (ref "con12") (pin "70") (pinfunction "70_70") (pintype "passive"))
      (node (ref "con12") (pin "72") (pinfunction "72_72") (pintype "passive"))
    )
    (net (code "132") (name "WIFI_CLK") (class "Default")
      (node (ref "CON10") (pin "37") (pinfunction "37_37") (pintype "passive"))
    )
    (net (code "133") (name "WIFI_CMD") (class "Default")
      (node (ref "CON10") (pin "38") (pinfunction "38_38") (pintype "passive"))
    )
    (net (code "134") (name "WIFI_D0") (class "Default")
      (node (ref "CON10") (pin "41") (pinfunction "41_41") (pintype "passive"))
    )
    (net (code "135") (name "WIFI_D1") (class "Default")
      (node (ref "CON10") (pin "40") (pinfunction "40_40") (pintype "passive"))
    )
    (net (code "136") (name "WIFI_D2") (class "Default")
      (node (ref "CON10") (pin "43") (pinfunction "43_43") (pintype "passive"))
    )
    (net (code "137") (name "WIFI_D3") (class "Default")
      (node (ref "CON10") (pin "42") (pinfunction "42_42") (pintype "passive"))
    )
    (net (code "138") (name "WIFI_PWDN") (class "Default")
      (node (ref "CON10") (pin "36") (pinfunction "36_36") (pintype "passive"))
    )
    (net (code "139") (name "WIFI_WOW") (class "Default")
      (node (ref "CON10") (pin "35") (pinfunction "35_35") (pintype "passive"))
    )
    (net (code "140") (name "W_PMU_EN") (class "Default")
      (node (ref "CON13") (pin "8") (pinfunction "8_8") (pintype "passive"))
    )
    (net (code "141") (name "XCLKOUT") (class "Default")
      (node (ref "CON10") (pin "59") (pinfunction "59_59") (pintype "passive"))
    )
    (net (code "142") (name "XEINT1_BAK") (class "Default")
      (node (ref "CON13") (pin "16") (pinfunction "16_16") (pintype "passive"))
    )
    (net (code "143") (name "XEINT6") (class "Default")
      (node (ref "CON13") (pin "18") (pinfunction "18_18") (pintype "passive"))
      (node (ref "R5") (pin "2") (pinfunction "2_2") (pintype "passive"))
      (node (ref "R56") (pin "2") (pinfunction "2_2") (pintype "passive"))
    )
    (net (code "144") (name "XEINT7{slash}GPX0_7") (class "Default")
      (node (ref "CON10") (pin "32") (pinfunction "32_32") (pintype "passive"))
    )
    (net (code "145") (name "XEINT14_BAK") (class "Default")
      (node (ref "CON13") (pin "22") (pinfunction "22_22") (pintype "passive"))
    )
    (net (code "146") (name "XEINT18{slash}KP_ROW2{slash}ALV_DBG14") (class "Default")
      (node (ref "CON10") (pin "48") (pinfunction "48_48") (pintype "passive"))
    )
    (net (code "147") (name "XEINT29{slash}KP_ROW13{slash}ALV_DBG25") (class "Default")
      (node (ref "CON10") (pin "49") (pinfunction "49_49") (pintype "passive"))
    )
    (net (code "148") (name "XEINT30{slash}HDMI_CEC{slash}ALV_DBG26") (class "Default")
      (node (ref "CON11") (pin "22") (pinfunction "22_22") (pintype "passive"))
    )
    (net (code "149") (name "XOM2") (class "Default")
      (node (ref "CON13") (pin "9") (pinfunction "9_9") (pintype "passive"))
      (node (ref "R53") (pin "2") (pinfunction "2_2") (pintype "passive"))
    )
    (net (code "150") (name "XOM3") (class "Default")
      (node (ref "CON13") (pin "10") (pinfunction "10_10") (pintype "passive"))
      (node (ref "CON13") (pin "11") (pinfunction "11_11") (pintype "passive"))
      (node (ref "R54") (pin "2") (pinfunction "2_2") (pintype "passive"))
    )
    (net (code "151") (name "XPWMTOUT1") (class "Default")
      (node (ref "CON13") (pin "5") (pinfunction "5_5") (pintype "passive"))
    )
    (net (code "152") (name "XUCTS1") (class "Default")
      (node (ref "con12") (pin "65") (pinfunction "65_65") (pintype "passive"))
    )
    (net (code "153") (name "XUHOSTDATA0") (class "Default")
      (node (ref "CON10") (pin "77") (pinfunction "77_77") (pintype "passive"))
    )
    (net (code "154") (name "XUHOSTDATA1_EXT") (class "Default")
      (node (ref "CON10") (pin "9") (pinfunction "9_9") (pintype "passive"))
    )
    (net (code "155") (name "XUHOSTSTROBE0") (class "Default")
      (node (ref "CON10") (pin "78") (pinfunction "78_78") (pintype "passive"))
    )
    (net (code "156") (name "XUHOSTSTROBE1_EXT") (class "Default")
      (node (ref "CON10") (pin "10") (pinfunction "10_10") (pintype "passive"))
    )
    (net (code "157") (name "XURTS1") (class "Default")
      (node (ref "con12") (pin "62") (pinfunction "62_62") (pintype "passive"))
    )
    (net (code "158") (name "XadcAIN0") (class "Default")
      (node (ref "CON11") (pin "49") (pinfunction "49_49") (pintype "passive"))
    )
    (net (code "159") (name "XadcAIN1") (class "Default")
      (node (ref "CON11") (pin "51") (pinfunction "51_51") (pintype "passive"))
    )
    (net (code "160") (name "XadcAIN2") (class "Default")
      (node (ref "CON11") (pin "53") (pinfunction "53_53") (pintype "passive"))
    )
    (net (code "161") (name "XadcAIN3") (class "Default")
      (node (ref "CON11") (pin "55") (pinfunction "55_55") (pintype "passive"))
    )
    (net (code "162") (name "XciFIELD") (class "Default")
      (node (ref "CON11") (pin "40") (pinfunction "40_40") (pintype "passive"))
    )
    (net (code "163") (name "XhdmiTX0N") (class "Default")
      (node (ref "CON11") (pin "9") (pinfunction "9_9") (pintype "passive"))
    )
    (net (code "164") (name "XhdmiTX0P") (class "Default")
      (node (ref "CON11") (pin "7") (pinfunction "7_7") (pintype "passive"))
    )
    (net (code "165") (name "XhdmiTX1N") (class "Default")
      (node (ref "CON11") (pin "10") (pinfunction "10_10") (pintype "passive"))
    )
    (net (code "166") (name "XhdmiTX1P") (class "Default")
      (node (ref "CON11") (pin "8") (pinfunction "8_8") (pintype "passive"))
    )
    (net (code "167") (name "XhdmiTX2N") (class "Default")
      (node (ref "CON11") (pin "15") (pinfunction "15_15") (pintype "passive"))
    )
    (net (code "168") (name "XhdmiTX2P") (class "Default")
      (node (ref "CON11") (pin "13") (pinfunction "13_13") (pintype "passive"))
    )
    (net (code "169") (name "XhdmiTXCN") (class "Default")
      (node (ref "CON11") (pin "16") (pinfunction "16_16") (pintype "passive"))
    )
    (net (code "170") (name "XhdmiTXCP") (class "Default")
      (node (ref "CON11") (pin "14") (pinfunction "14_14") (pintype "passive"))
    )
    (net (code "171") (name "Xi2s0CDCLK{slash}PCM_0_EXTCLK") (class "Default")
      (node (ref "CON11") (pin "71") (pinfunction "71_71") (pintype "passive"))
    )
    (net (code "172") (name "Xi2s0LRCK{slash}PCM_0_FSYNC") (class "Default")
      (node (ref "CON11") (pin "70") (pinfunction "70_70") (pintype "passive"))
    )
    (net (code "173") (name "Xi2s0SCLK{slash}PCM_0_SCLK") (class "Default")
      (node (ref "CON11") (pin "68") (pinfunction "68_68") (pintype "passive"))
    )
    (net (code "174") (name "Xi2s0SDI{slash}PCM_0_SIN") (class "Default")
      (node (ref "CON11") (pin "74") (pinfunction "74_74") (pintype "passive"))
    )
    (net (code "175") (name "Xi2s0SDO_0{slash}PCM_0_SOUT") (class "Default")
      (node (ref "CON11") (pin "72") (pinfunction "72_72") (pintype "passive"))
    )
    (net (code "176") (name "XispI2C1SCL") (class "Default")
      (node (ref "CON13") (pin "30") (pinfunction "30_30") (pintype "passive"))
    )
    (net (code "177") (name "XispI2C1SDA") (class "Default")
      (node (ref "CON13") (pin "32") (pinfunction "32_32") (pintype "passive"))
    )
    (net (code "178") (name "XispSPICLK") (class "Default")
      (node (ref "CON13") (pin "26") (pinfunction "26_26") (pintype "passive"))
    )
    (net (code "179") (name "XispSPICSn") (class "Default")
      (node (ref "CON13") (pin "19") (pinfunction "19_19") (pintype "passive"))
    )
    (net (code "180") (name "XispSPIMISO") (class "Default")
      (node (ref "CON13") (pin "21") (pinfunction "21_21") (pintype "passive"))
    )
    (net (code "181") (name "XispSPIMOSI") (class "Default")
      (node (ref "CON13") (pin "28") (pinfunction "28_28") (pintype "passive"))
    )
    (net (code "182") (name "XjTCK") (class "Default")
      (node (ref "CON13") (pin "13") (pinfunction "13_13") (pintype "passive"))
    )
    (net (code "183") (name "XjTDI") (class "Default")
      (node (ref "CON13") (pin "14") (pinfunction "14_14") (pintype "passive"))
    )
    (net (code "184") (name "XjTDO") (class "Default")
      (node (ref "CON13") (pin "15") (pinfunction "15_15") (pintype "passive"))
    )
    (net (code "185") (name "XjTMS") (class "Default")
      (node (ref "CON13") (pin "12") (pinfunction "12_12") (pintype "passive"))
    )
    (net (code "186") (name "XjTRSTn") (class "Default")
      (node (ref "CON13") (pin "17") (pinfunction "17_17") (pintype "passive"))
    )
    (net (code "187") (name "Xm0ADDR0") (class "Default")
      (node (ref "CON13") (pin "65") (pinfunction "65_65") (pintype "passive"))
    )
    (net (code "188") (name "Xm0ADDR1") (class "Default")
      (node (ref "CON13") (pin "68") (pinfunction "68_68") (pintype "passive"))
    )
    (net (code "189") (name "Xm0ADDR2") (class "Default")
      (node (ref "CON13") (pin "67") (pinfunction "67_67") (pintype "passive"))
    )
    (net (code "190") (name "Xm0ADDR3") (class "Default")
      (node (ref "CON13") (pin "70") (pinfunction "70_70") (pintype "passive"))
    )
    (net (code "191") (name "Xm0ADDR4") (class "Default")
      (node (ref "CON13") (pin "69") (pinfunction "69_69") (pintype "passive"))
    )
    (net (code "192") (name "Xm0ADDR5") (class "Default")
      (node (ref "CON13") (pin "72") (pinfunction "72_72") (pintype "passive"))
    )
    (net (code "193") (name "Xm0ADDR6") (class "Default")
      (node (ref "CON13") (pin "71") (pinfunction "71_71") (pintype "passive"))
    )
    (net (code "194") (name "Xm0ADDR7") (class "Default")
      (node (ref "CON13") (pin "74") (pinfunction "74_74") (pintype "passive"))
    )
    (net (code "196") (name "Xm0BEn0") (class "Default")
      (node (ref "CON13") (pin "43") (pinfunction "43_43") (pintype "passive"))
    )
    (net (code "197") (name "Xm0DATA0") (class "Default")
      (node (ref "CON13") (pin "45") (pinfunction "45_45") (pintype "passive"))
    )
    (net (code "198") (name "Xm0DATA1") (class "Default")
      (node (ref "CON13") (pin "50") (pinfunction "50_50") (pintype "passive"))
    )
    (net (code "199") (name "Xm0DATA2") (class "Default")
      (node (ref "CON13") (pin "47") (pinfunction "47_47") (pintype "passive"))
    )
    (net (code "200") (name "Xm0DATA3") (class "Default")
      (node (ref "CON13") (pin "52") (pinfunction "52_52") (pintype "passive"))
    )
    (net (code "201") (name "Xm0DATA4") (class "Default")
      (node (ref "CON13") (pin "49") (pinfunction "49_49") (pintype "passive"))
    )
    (net (code "202") (name "Xm0DATA5") (class "Default")
      (node (ref "CON13") (pin "54") (pinfunction "54_54") (pintype "passive"))
    )
    (net (code "203") (name "Xm0DATA6") (class "Default")
      (node (ref "CON13") (pin "51") (pinfunction "51_51") (pintype "passive"))
    )
    (net (code "204") (name "Xm0DATA7") (class "Default")
      (node (ref "CON13") (pin "56") (pinfunction "56_56") (pintype "passive"))
    )
    (net (code "205") (name "Xm0DATA8") (class "Default")
      (node (ref "CON13") (pin "55") (pinfunction "55_55") (pintype "passive"))
    )
    (net (code "206") (name "Xm0DATA9") (class "Default")
      (node (ref "CON13") (pin "58") (pinfunction "58_58") (pintype "passive"))
    )
    (net (code "207") (name "Xm0DATA10") (class "Default")
      (node (ref "CON13") (pin "57") (pinfunction "57_57") (pintype "passive"))
    )
    (net (code "208") (name "Xm0DATA11") (class "Default")
      (node (ref "CON13") (pin "60") (pinfunction "60_60") (pintype "passive"))
    )
    (net (code "209") (name "Xm0DATA12") (class "Default")
      (node (ref "CON13") (pin "59") (pinfunction "59_59") (pintype "passive"))
    )
    (net (code "210") (name "Xm0DATA13") (class "Default")
      (node (ref "CON13") (pin "62") (pinfunction "62_62") (pintype "passive"))
    )
    (net (code "211") (name "Xm0DATA14") (class "Default")
      (node (ref "CON13") (pin "61") (pinfunction "61_61") (pintype "passive"))
    )
    (net (code "212") (name "Xm0DATA15") (class "Default")
      (node (ref "CON13") (pin "64") (pinfunction "64_64") (pintype "passive"))
    )
    (net (code "214") (name "Xm0DATA_RDn") (class "Default")
      (node (ref "CON13") (pin "44") (pinfunction "44_44") (pintype "passive"))
    )
    (net (code "215") (name "Xm0OEn") (class "Default")
      (node (ref "CON13") (pin "48") (pinfunction "48_48") (pintype "passive"))
    )
    (net (code "216") (name "Xm0WEn") (class "Default")
      (node (ref "CON13") (pin "41") (pinfunction "41_41") (pintype "passive"))
    )
    (net (code "217") (name "Xm0cs0") (class "Default")
      (node (ref "CON13") (pin "73") (pinfunction "73_73") (pintype "passive"))
    )
    (net (code "218") (name "Xm0cs1") (class "Default")
      (node (ref "CON13") (pin "46") (pinfunction "46_46") (pintype "passive"))
    )
    (net (code "219") (name "Xmipi2LSDN0") (class "Default")
      (node (ref "CON11") (pin "64") (pinfunction "64_64") (pintype "passive"))
    )
    (net (code "220") (name "Xmipi2LSDN1") (class "Default")
      (node (ref "CON11") (pin "67") (pinfunction "67_67") (pintype "passive"))
    )
    (net (code "221") (name "Xmipi2LSDNCLK") (class "Default")
      (node (ref "CON11") (pin "61") (pinfunction "61_61") (pintype "passive"))
    )
    (net (code "222") (name "Xmipi2LSDP0") (class "Default")
      (node (ref "CON11") (pin "62") (pinfunction "62_62") (pintype "passive"))
    )
    (net (code "223") (name "Xmipi2LSDP1") (class "Default")
      (node (ref "CON11") (pin "65") (pinfunction "65_65") (pintype "passive"))
    )
    (net (code "224") (name "Xmipi2LSDPCLK") (class "Default")
      (node (ref "CON11") (pin "59") (pinfunction "59_59") (pintype "passive"))
    )
    (net (code "225") (name "XmipiMDN0") (class "Default")
      (node (ref "CON13") (pin "29") (pinfunction "29_29") (pintype "passive"))
    )
    (net (code "226") (name "XmipiMDN1") (class "Default")
      (node (ref "CON13") (pin "33") (pinfunction "33_33") (pintype "passive"))
    )
    (net (code "227") (name "XmipiMDN2") (class "Default")
      (node (ref "CON13") (pin "38") (pinfunction "38_38") (pintype "passive"))
    )
    (net (code "228") (name "XmipiMDN3") (class "Default")
      (node (ref "CON13") (pin "42") (pinfunction "42_42") (pintype "passive"))
    )
    (net (code "229") (name "XmipiMDNCLK") (class "Default")
      (node (ref "CON13") (pin "37") (pinfunction "37_37") (pintype "passive"))
    )
    (net (code "230") (name "XmipiMDP0") (class "Default")
      (node (ref "CON13") (pin "27") (pinfunction "27_27") (pintype "passive"))
    )
    (net (code "231") (name "XmipiMDP1") (class "Default")
      (node (ref "CON13") (pin "31") (pinfunction "31_31") (pintype "passive"))
    )
    (net (code "232") (name "XmipiMDP2") (class "Default")
      (node (ref "CON13") (pin "36") (pinfunction "36_36") (pintype "passive"))
    )
    (net (code "233") (name "XmipiMDP3") (class "Default")
      (node (ref "CON13") (pin "40") (pinfunction "40_40") (pintype "passive"))
    )
    (net (code "234") (name "XmipiMDPCLK") (class "Default")
      (node (ref "CON13") (pin "35") (pinfunction "35_35") (pintype "passive"))
    )
    (net (code "235") (name "Xmmc2CLK") (class "Default")
      (node (ref "CON10") (pin "26") (pinfunction "26_26") (pintype "passive"))
    )
    (net (code "236") (name "Xmmc2CMD") (class "Default")
      (node (ref "CON10") (pin "23") (pinfunction "23_23") (pintype "passive"))
    )
    (net (code "237") (name "Xmmc2DATA0") (class "Default")
      (node (ref "CON10") (pin "28") (pinfunction "28_28") (pintype "passive"))
    )
    (net (code "238") (name "Xmmc2DATA1") (class "Default")
      (node (ref "CON10") (pin "30") (pinfunction "30_30") (pintype "passive"))
    )
    (net (code "239") (name "Xmmc2DATA2") (class "Default")
      (node (ref "CON10") (pin "25") (pinfunction "25_25") (pintype "passive"))
    )
    (net (code "240") (name "Xmmc2DATA3") (class "Default")
      (node (ref "CON10") (pin "27") (pinfunction "27_27") (pintype "passive"))
    )
    (net (code "241") (name "XnRESET_EXT") (class "Default")
      (node (ref "CON10") (pin "61") (pinfunction "61_61") (pintype "passive"))
    )
    (net (code "242") (name "XnRSOUT") (class "Default")
      (node (ref "CON10") (pin "64") (pinfunction "64_64") (pintype "passive"))
    )
    (net (code "243") (name "XnWRESET") (class "Default")
      (node (ref "CON10") (pin "62") (pinfunction "62_62") (pintype "passive"))
    )
    (net (code "244") (name "XspiCLK0{slash}I2C_4_SDA") (class "Default")
      (node (ref "CON11") (pin "73") (pinfunction "73_73") (pintype "passive"))
    )
    (net (code "245") (name "XspiCSn0{slash}I2C_4_SCL") (class "Default")
      (node (ref "CON11") (pin "76") (pinfunction "76_76") (pintype "passive"))
    )
    (net (code "246") (name "XuCTSn0") (class "Default")
      (node (ref "CON10") (pin "46") (pinfunction "46_46") (pintype "passive"))
    )
    (net (code "247") (name "XuCTSn2{slash}I2C_3_SDA") (class "Default")
      (node (ref "con12") (pin "51") (pinfunction "51_51") (pintype "passive"))
    )
    (net (code "248") (name "XuRTSn0") (class "Default")
      (node (ref "CON10") (pin "47") (pinfunction "47_47") (pintype "passive"))
    )
    (net (code "249") (name "XuRTSn2{slash}I2C_3_SCL") (class "Default")
      (node (ref "con12") (pin "49") (pinfunction "49_49") (pintype "passive"))
    )
    (net (code "250") (name "XuRXD0") (class "Default")
      (node (ref "CON10") (pin "44") (pinfunction "44_44") (pintype "passive"))
    )
    (net (code "251") (name "XuRXD1") (class "Default")
      (node (ref "con12") (pin "60") (pinfunction "60_60") (pintype "passive"))
    )
    (net (code "252") (name "XuRXD2{slash}UART_AUDIO_RXD") (class "Default")
      (node (ref "con12") (pin "54") (pinfunction "54_54") (pintype "passive"))
    )
    (net (code "253") (name "XuTXD0") (class "Default")
      (node (ref "CON10") (pin "45") (pinfunction "45_45") (pintype "passive"))
    )
    (net (code "254") (name "XuTXD1") (class "Default")
      (node (ref "con12") (pin "63") (pinfunction "63_63") (pintype "passive"))
    )
    (net (code "255") (name "XuTXD2{slash}UART_AUDIO_TXD") (class "Default")
      (node (ref "con12") (pin "56") (pinfunction "56_56") (pintype "passive"))
    )
    (net (code "256") (name "XuotgDM") (class "Default")
      (node (ref "CON10") (pin "16") (pinfunction "16_16") (pintype "passive"))
    )
    (net (code "257") (name "XuotgDP") (class "Default")
      (node (ref "CON10") (pin "14") (pinfunction "14_14") (pintype "passive"))
    )
    (net (code "258") (name "XuotgID") (class "Default")
      (node (ref "CON10") (pin "12") (pinfunction "12_12") (pintype "passive"))
    )
    (net (code "259") (name "XuotgVBUS") (class "Default")
      (node (ref "CON11") (pin "24") (pinfunction "24_24") (pintype "passive"))
    )
    (net (code "260") (name "XvSYS_OE") (class "Default")
      (node (ref "CON13") (pin "39") (pinfunction "39_39") (pintype "passive"))
    )
    (net (code "261") (name "XvVSYNC_LDI") (class "Default")
      (node (ref "CON13") (pin "34") (pinfunction "34_34") (pintype "passive"))
    )
    (net (code "262") (name "unconnected-(U22-PGOOD-Pad8)") (class "Default")
      (node (ref "U22") (pin "8") (pinfunction "PGOOD_8") (pintype "passive"))
    )
    (net (code "263") (name "unconnected-(con12-Pad11)") (class "Default")
      (node (ref "con12") (pin "11") (pinfunction "11_11") (pintype "passive"))
    )
    (net (code "264") (name "unconnected-(con12-Pad13)") (class "Default")
      (node (ref "con12") (pin "13") (pinfunction "13_13") (pintype "passive"))
    )
    (net (code "265") (name "unconnected-(con12-Pad71)") (class "Default")
      (node (ref "con12") (pin "71") (pinfunction "71_71") (pintype "passive"))
    )
    (net (code "266") (name "unconnected-(con12-Pad73)") (class "Default")
      (node (ref "con12") (pin "73") (pinfunction "73_73") (pintype "passive"))
    )
  )
)
